# Oda_Lambas_V0_01.net
KiCad netlist of a schematic drawn in EAGLE
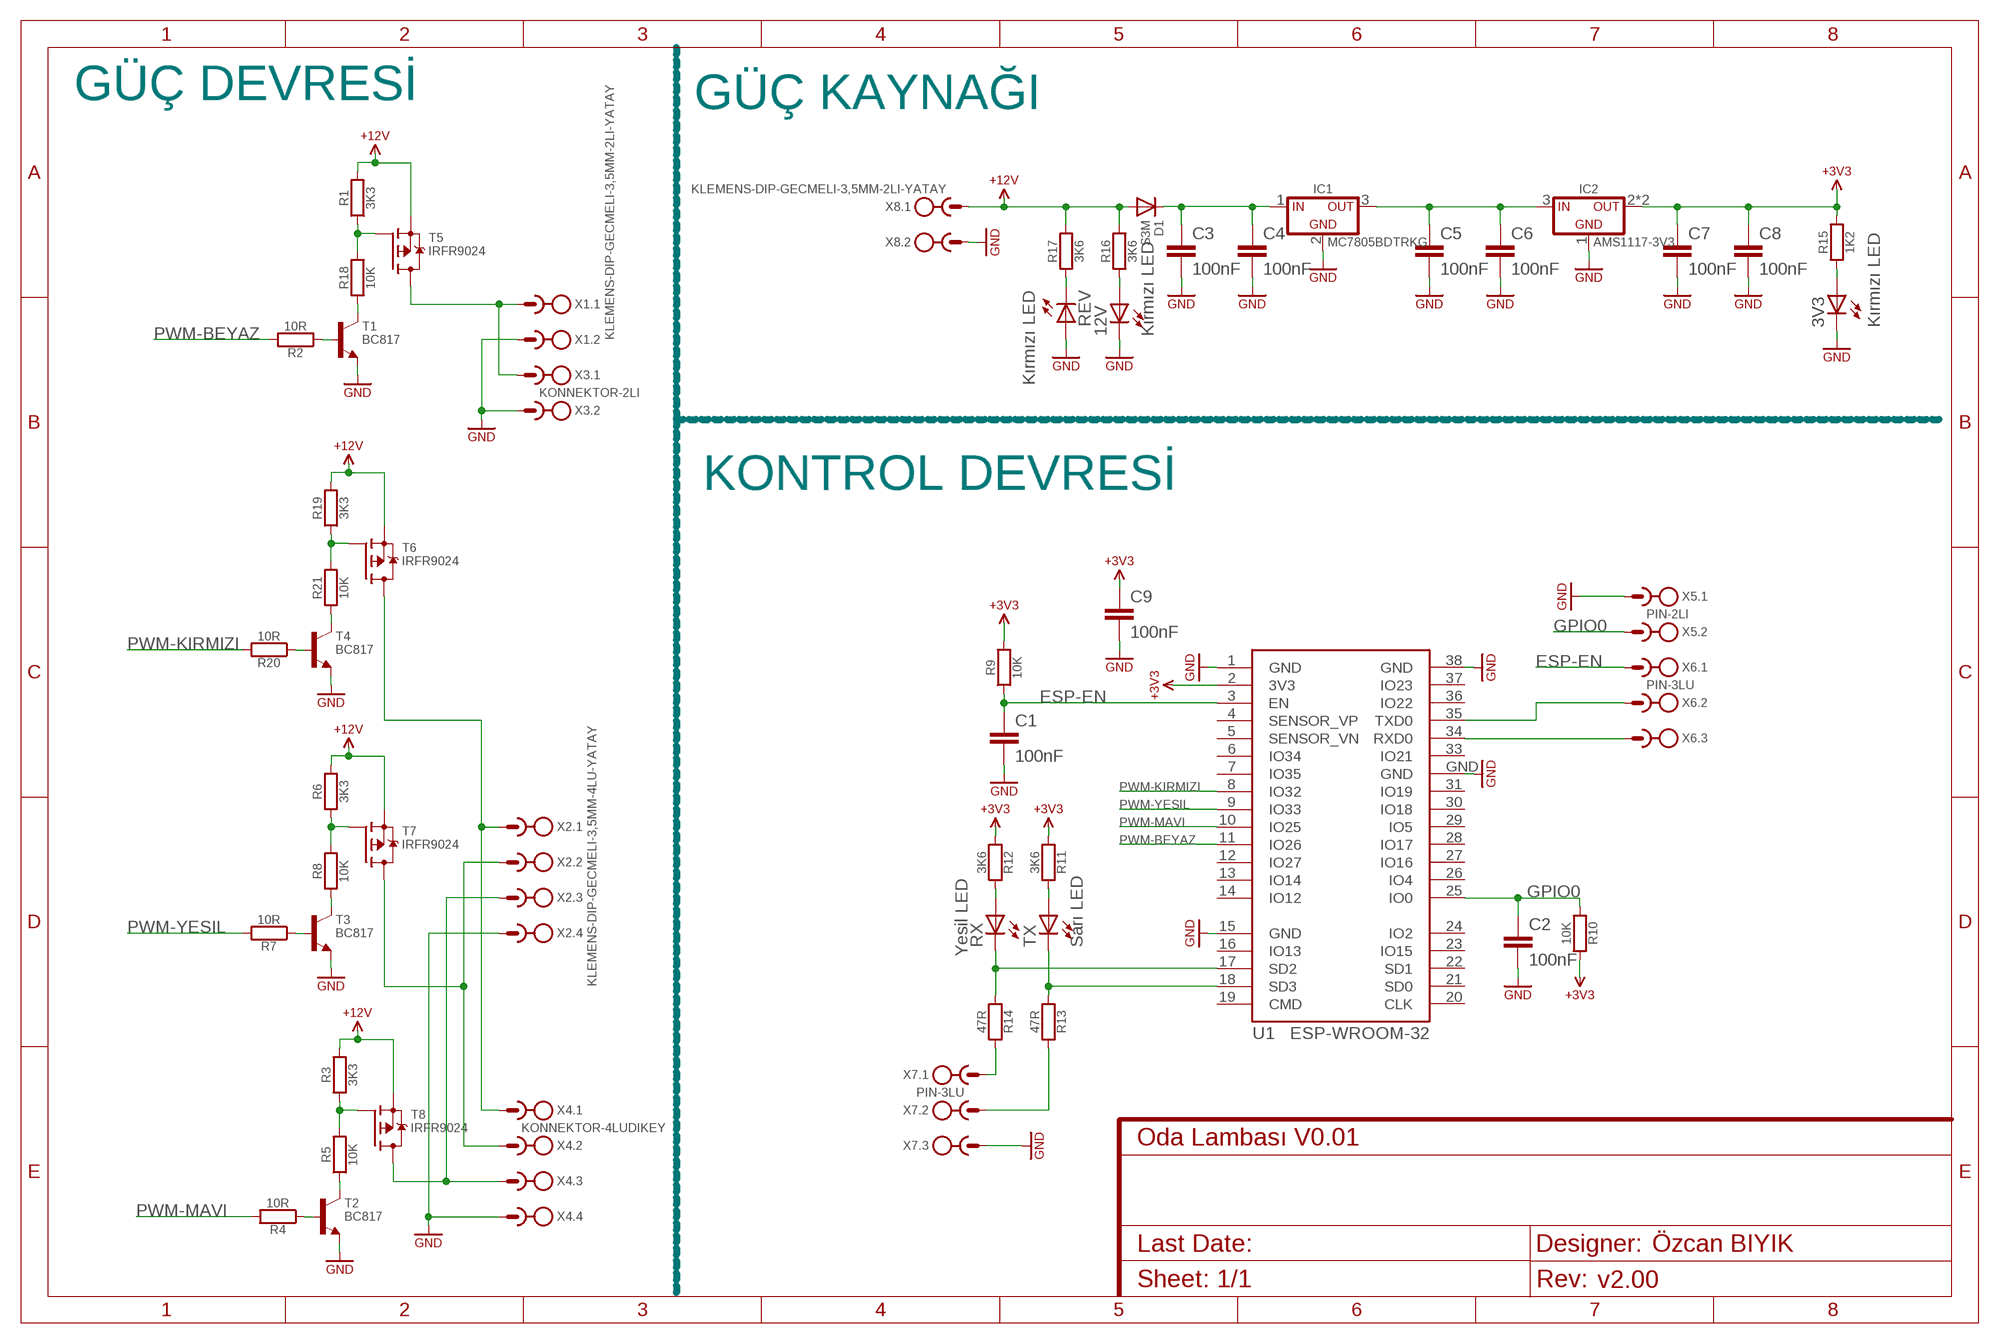
[diagram p0: schematic, sheet 1]

(export (version "E")
  (design (tool "Eeschema 10.0.6"))
  (components
    (comp (ref "3V3")
      (value "Kırmızı LED")
      (footprint "eagle-import:0805")
      (libsource (lib "eagle-import") (part "LED"))
    )
    (comp (ref "12V")
      (value "Kırmızı LED")
      (footprint "eagle-import:0805")
      (libsource (lib "eagle-import") (part "LED"))
    )
    (comp (ref "C1")
      (value "100nF")
      (footprint "eagle-import:C1206")
      (libsource (lib "eagle-import") (part "CAP1206"))
    )
    (comp (ref "C2")
      (value "100nF")
      (footprint "eagle-import:C1206")
      (libsource (lib "eagle-import") (part "CAP1206"))
    )
    (comp (ref "C3")
      (value "100nF")
      (footprint "eagle-import:C1206")
      (libsource (lib "eagle-import") (part "CAP1206"))
    )
    (comp (ref "C4")
      (value "100nF")
      (footprint "eagle-import:C1206")
      (libsource (lib "eagle-import") (part "CAP1206"))
    )
    (comp (ref "C5")
      (value "100nF")
      (footprint "eagle-import:C1206")
      (libsource (lib "eagle-import") (part "CAP1206"))
    )
    (comp (ref "C6")
      (value "100nF")
      (footprint "eagle-import:C1206")
      (libsource (lib "eagle-import") (part "CAP1206"))
    )
    (comp (ref "C7")
      (value "100nF")
      (footprint "eagle-import:C1206")
      (libsource (lib "eagle-import") (part "CAP1206"))
    )
    (comp (ref "C8")
      (value "100nF")
      (footprint "eagle-import:C1206")
      (libsource (lib "eagle-import") (part "CAP1206"))
    )
    (comp (ref "C9")
      (value "100nF")
      (footprint "eagle-import:C1206")
      (libsource (lib "eagle-import") (part "CAP1206"))
    )
    (comp (ref "D1")
      (value "S3M")
      (footprint "eagle-import:SMC")
      (libsource (lib "eagle-import") (part "S3M"))
    )
    (comp (ref "IC1")
      (value "MC7805BDTRKG")
      (footprint "eagle-import:DPAK")
      (libsource (lib "eagle-import") (part "MC7805BDTRKG"))
    )
    (comp (ref "IC2")
      (value "AMS1117-3V3")
      (footprint "eagle-import:SOT223")
      (libsource (lib "eagle-import") (part "FAN1117A"))
    )
    (comp (ref "R1")
      (value "3K3")
      (footprint "eagle-import:R1206")
      (libsource (lib "eagle-import") (part "RES1206"))
    )
    (comp (ref "R2")
      (value "10R")
      (footprint "eagle-import:R1206")
      (libsource (lib "eagle-import") (part "RES1206"))
    )
    (comp (ref "R3")
      (value "3K3")
      (footprint "eagle-import:R1206")
      (libsource (lib "eagle-import") (part "RES1206"))
    )
    (comp (ref "R4")
      (value "10R")
      (footprint "eagle-import:R1206")
      (libsource (lib "eagle-import") (part "RES1206"))
    )
    (comp (ref "R5")
      (value "10K")
      (footprint "eagle-import:R1206")
      (libsource (lib "eagle-import") (part "RES1206"))
    )
    (comp (ref "R6")
      (value "3K3")
      (footprint "eagle-import:R1206")
      (libsource (lib "eagle-import") (part "RES1206"))
    )
    (comp (ref "R7")
      (value "10R")
      (footprint "eagle-import:R1206")
      (libsource (lib "eagle-import") (part "RES1206"))
    )
    (comp (ref "R8")
      (value "10K")
      (footprint "eagle-import:R1206")
      (libsource (lib "eagle-import") (part "RES1206"))
    )
    (comp (ref "R9")
      (value "10K")
      (footprint "eagle-import:R1206")
      (libsource (lib "eagle-import") (part "RES1206"))
    )
    (comp (ref "R10")
      (value "10K")
      (footprint "eagle-import:R1206")
      (libsource (lib "eagle-import") (part "RES1206"))
    )
    (comp (ref "R11")
      (value "3K6")
      (footprint "eagle-import:R1206")
      (libsource (lib "eagle-import") (part "RES1206"))
    )
    (comp (ref "R12")
      (value "3K6")
      (footprint "eagle-import:R1206")
      (libsource (lib "eagle-import") (part "RES1206"))
    )
    (comp (ref "R13")
      (value "47R")
      (footprint "eagle-import:R1206")
      (libsource (lib "eagle-import") (part "RES1206"))
    )
    (comp (ref "R14")
      (value "47R")
      (footprint "eagle-import:R1206")
      (libsource (lib "eagle-import") (part "RES1206"))
    )
    (comp (ref "R15")
      (value "1K2")
      (footprint "eagle-import:R1206")
      (libsource (lib "eagle-import") (part "RES1206"))
    )
    (comp (ref "R16")
      (value "3K6")
      (footprint "eagle-import:R1206")
      (libsource (lib "eagle-import") (part "RES1206"))
    )
    (comp (ref "R17")
      (value "3K6")
      (footprint "eagle-import:R1206")
      (libsource (lib "eagle-import") (part "RES1206"))
    )
    (comp (ref "R18")
      (value "10K")
      (footprint "eagle-import:R1206")
      (libsource (lib "eagle-import") (part "RES1206"))
    )
    (comp (ref "R19")
      (value "3K3")
      (footprint "eagle-import:R1206")
      (libsource (lib "eagle-import") (part "RES1206"))
    )
    (comp (ref "R20")
      (value "10R")
      (footprint "eagle-import:R1206")
      (libsource (lib "eagle-import") (part "RES1206"))
    )
    (comp (ref "R21")
      (value "10K")
      (footprint "eagle-import:R1206")
      (libsource (lib "eagle-import") (part "RES1206"))
    )
    (comp (ref "REV")
      (value "Kırmızı LED")
      (footprint "eagle-import:0805")
      (libsource (lib "eagle-import") (part "LED"))
    )
    (comp (ref "RX")
      (value "Yesil LED")
      (footprint "eagle-import:0805")
      (libsource (lib "eagle-import") (part "LED"))
    )
    (comp (ref "T1")
      (value "BC817")
      (footprint "eagle-import:SOT23")
      (libsource (lib "eagle-import") (part "BC817"))
    )
    (comp (ref "T2")
      (value "BC817")
      (footprint "eagle-import:SOT23")
      (libsource (lib "eagle-import") (part "BC817"))
    )
    (comp (ref "T3")
      (value "BC817")
      (footprint "eagle-import:SOT23")
      (libsource (lib "eagle-import") (part "BC817"))
    )
    (comp (ref "T4")
      (value "BC817")
      (footprint "eagle-import:SOT23")
      (libsource (lib "eagle-import") (part "BC817"))
    )
    (comp (ref "T5")
      (value "IRFR9024")
      (footprint "eagle-import:DPAK")
      (libsource (lib "eagle-import") (part "IRFR9024"))
    )
    (comp (ref "T6")
      (value "IRFR9024")
      (footprint "eagle-import:DPAK")
      (libsource (lib "eagle-import") (part "IRFR9024"))
    )
    (comp (ref "T7")
      (value "IRFR9024")
      (footprint "eagle-import:DPAK")
      (libsource (lib "eagle-import") (part "IRFR9024"))
    )
    (comp (ref "T8")
      (value "IRFR9024")
      (footprint "eagle-import:DPAK")
      (libsource (lib "eagle-import") (part "IRFR9024"))
    )
    (comp (ref "TX")
      (value "Sarı LED")
      (footprint "eagle-import:0805")
      (libsource (lib "eagle-import") (part "LED"))
    )
    (comp (ref "U1")
      (value "ESP-WROOM-32")
      (footprint "eagle-import:ESP-WROOM-32")
      (libsource (lib "eagle-import") (part "ESP-WROOM-32"))
    )
    (comp (ref "X1")
      (value "KLEMENS-DIP-GECMELI-3,5MM-2LI-YATAY")
      (footprint "eagle-import:KLEMENS-DIP-GECMELI-3,5MM-2LI-YATAY")
      (libsource (lib "eagle-import") (part "KLEMENS-DIP-GECMELI-3,5MM-2LI-YATAY"))
    )
    (comp (ref "X2")
      (value "KLEMENS-DIP-GECMELI-3,5MM-4LU-YATAY")
      (footprint "eagle-import:KLEMENS-DIP-GECMELI-3,5MM-4LU-YATAY")
      (libsource (lib "eagle-import") (part "KLEMENS-DIP-GECMELI-3,5MM-4LU-YATAY"))
    )
    (comp (ref "X3")
      (value "KONNEKTOR-2LI")
      (footprint "eagle-import:MOLEX-DIP-2LI-YATAY")
      (libsource (lib "eagle-import") (part "KONNEKTOR-2LI"))
    )
    (comp (ref "X4")
      (value "KONNEKTOR-4LUDIKEY")
      (footprint "eagle-import:MOLEX-DIP-4LU-DIKEY")
      (libsource (lib "eagle-import") (part "KONNEKTOR-4LUDIKEY"))
    )
    (comp (ref "X5")
      (value "PIN-2LI")
      (footprint "eagle-import:PINHEADER-DIP-2-2.54")
      (libsource (lib "eagle-import") (part "PIN-2LI"))
    )
    (comp (ref "X6")
      (value "PIN-3LU")
      (footprint "eagle-import:PINHEADER-DIP-3-2.54")
      (libsource (lib "eagle-import") (part "PIN-3LU"))
    )
    (comp (ref "X7")
      (value "PIN-3LU")
      (footprint "eagle-import:PINHEADER-DIP-3-2.54")
      (libsource (lib "eagle-import") (part "PIN-3LU"))
    )
    (comp (ref "X8")
      (value "KLEMENS-DIP-GECMELI-3,5MM-2LI-YATAY")
      (footprint "eagle-import:KLEMENS-DIP-GECMELI-3,5MM-2LI-YATAY")
      (libsource (lib "eagle-import") (part "KLEMENS-DIP-GECMELI-3,5MM-2LI-YATAY"))
    )
  )
  (nets
    (net (code "1") (name "+3V3") (class "Default")
      (node (ref "C7") (pin "1") (pinfunction "1_1") (pintype "passive"))
      (node (ref "C8") (pin "1") (pinfunction "1_1") (pintype "passive"))
      (node (ref "C9") (pin "1") (pinfunction "1_1") (pintype "passive"))
      (node (ref "IC2") (pin "2") (pinfunction "OUT_2") (pintype "passive"))
      (node (ref "IC2") (pin "4") (pinfunction "OUT_4") (pintype "passive"))
      (node (ref "R10") (pin "2") (pinfunction "2_2") (pintype "passive"))
      (node (ref "R11") (pin "2") (pinfunction "2_2") (pintype "passive"))
      (node (ref "R12") (pin "2") (pinfunction "2_2") (pintype "passive"))
      (node (ref "R15") (pin "2") (pinfunction "2_2") (pintype "passive"))
      (node (ref "R9") (pin "2") (pinfunction "2_2") (pintype "passive"))
      (node (ref "U1") (pin "2") (pinfunction "3V3_2") (pintype "power_in"))
    )
    (net (code "2") (name "+12V") (class "Default")
      (node (ref "D1") (pin "A") (pinfunction "A_A") (pintype "passive"))
      (node (ref "R1") (pin "2") (pinfunction "2_2") (pintype "passive"))
      (node (ref "R16") (pin "2") (pinfunction "2_2") (pintype "passive"))
      (node (ref "R17") (pin "2") (pinfunction "2_2") (pintype "passive"))
      (node (ref "R19") (pin "2") (pinfunction "2_2") (pintype "passive"))
      (node (ref "R3") (pin "2") (pinfunction "2_2") (pintype "passive"))
      (node (ref "R6") (pin "2") (pinfunction "2_2") (pintype "passive"))
      (node (ref "T5") (pin "3") (pinfunction "S_3") (pintype "passive"))
      (node (ref "T6") (pin "3") (pinfunction "S_3") (pintype "passive"))
      (node (ref "T7") (pin "3") (pinfunction "S_3") (pintype "passive"))
      (node (ref "T8") (pin "3") (pinfunction "S_3") (pintype "passive"))
      (node (ref "X8") (pin "1") (pinfunction "1_1") (pintype "passive"))
    )
    (net (code "3") (name "/ESP-EN") (class "Default")
      (node (ref "C1") (pin "1") (pinfunction "1_1") (pintype "passive"))
      (node (ref "R9") (pin "1") (pinfunction "1_1") (pintype "passive"))
      (node (ref "U1") (pin "3") (pinfunction "EN_3") (pintype "input"))
      (node (ref "X6") (pin "1") (pinfunction "1_1") (pintype "passive"))
    )
    (net (code "4") (name "/GPIO0") (class "Default")
      (node (ref "C2") (pin "1") (pinfunction "1_1") (pintype "passive"))
      (node (ref "R10") (pin "1") (pinfunction "1_1") (pintype "passive"))
      (node (ref "U1") (pin "25") (pinfunction "IO0_25") (pintype "bidirectional"))
      (node (ref "X5") (pin "2") (pinfunction "1_2") (pintype "passive"))
    )
    (net (code "5") (name "/PWM-BEYAZ") (class "Default")
      (node (ref "R2") (pin "2") (pinfunction "2_2") (pintype "passive"))
      (node (ref "U1") (pin "11") (pinfunction "IO26_11") (pintype "bidirectional"))
    )
    (net (code "6") (name "/PWM-KIRMIZI") (class "Default")
      (node (ref "R20") (pin "2") (pinfunction "2_2") (pintype "passive"))
      (node (ref "U1") (pin "8") (pinfunction "IO32_8") (pintype "bidirectional"))
    )
    (net (code "7") (name "/PWM-MAVI") (class "Default")
      (node (ref "R4") (pin "2") (pinfunction "2_2") (pintype "passive"))
      (node (ref "U1") (pin "10") (pinfunction "IO25_10") (pintype "bidirectional"))
    )
    (net (code "8") (name "/PWM-YESIL") (class "Default")
      (node (ref "R7") (pin "2") (pinfunction "2_2") (pintype "passive"))
      (node (ref "U1") (pin "9") (pinfunction "IO33_9") (pintype "bidirectional"))
    )
    (net (code "9") (name "GND") (class "Default")
      (node (ref "12V") (pin "C") (pinfunction "C_C") (pintype "passive"))
      (node (ref "3V3") (pin "C") (pinfunction "C_C") (pintype "passive"))
      (node (ref "C1") (pin "2") (pinfunction "2_2") (pintype "passive"))
      (node (ref "C2") (pin "2") (pinfunction "2_2") (pintype "passive"))
      (node (ref "C3") (pin "2") (pinfunction "2_2") (pintype "passive"))
      (node (ref "C4") (pin "2") (pinfunction "2_2") (pintype "passive"))
      (node (ref "C5") (pin "2") (pinfunction "2_2") (pintype "passive"))
      (node (ref "C6") (pin "2") (pinfunction "2_2") (pintype "passive"))
      (node (ref "C7") (pin "2") (pinfunction "2_2") (pintype "passive"))
      (node (ref "C8") (pin "2") (pinfunction "2_2") (pintype "passive"))
      (node (ref "C9") (pin "2") (pinfunction "2_2") (pintype "passive"))
      (node (ref "IC1") (pin "2") (pinfunction "GND_2") (pintype "passive"))
      (node (ref "IC2") (pin "1") (pinfunction "GND_1") (pintype "passive"))
      (node (ref "REV") (pin "A") (pinfunction "A_A") (pintype "passive"))
      (node (ref "T1") (pin "2") (pinfunction "E_2") (pintype "passive"))
      (node (ref "T2") (pin "2") (pinfunction "E_2") (pintype "passive"))
      (node (ref "T3") (pin "2") (pinfunction "E_2") (pintype "passive"))
      (node (ref "T4") (pin "2") (pinfunction "E_2") (pintype "passive"))
      (node (ref "U1") (pin "1") (pinfunction "GND_1") (pintype "power_in"))
      (node (ref "U1") (pin "15") (pinfunction "GND_15") (pintype "power_in"))
      (node (ref "U1") (pin "38") (pinfunction "GND_38") (pintype "power_in"))
      (node (ref "U1") (pin "GND") (pinfunction "GND_GND") (pintype "power_in"))
      (node (ref "X1") (pin "2") (pinfunction "1_2") (pintype "passive"))
      (node (ref "X2") (pin "4") (pinfunction "1_4") (pintype "passive"))
      (node (ref "X3") (pin "2") (pinfunction "1_2") (pintype "passive"))
      (node (ref "X4") (pin "4") (pinfunction "1_4") (pintype "passive"))
      (node (ref "X5") (pin "1") (pinfunction "1_1") (pintype "passive"))
      (node (ref "X7") (pin "3") (pinfunction "1_3") (pintype "passive"))
      (node (ref "X8") (pin "2") (pinfunction "1_2") (pintype "passive"))
    )
    (net (code "10") (name "Net-(3V3-PadA)") (class "Default")
      (node (ref "3V3") (pin "A") (pinfunction "A_A") (pintype "passive"))
      (node (ref "R15") (pin "1") (pinfunction "1_1") (pintype "passive"))
    )
    (net (code "11") (name "Net-(12V-PadA)") (class "Default")
      (node (ref "12V") (pin "A") (pinfunction "A_A") (pintype "passive"))
      (node (ref "R16") (pin "1") (pinfunction "1_1") (pintype "passive"))
    )
    (net (code "12") (name "Net-(IC1-IN)") (class "Default")
      (node (ref "C3") (pin "1") (pinfunction "1_1") (pintype "passive"))
      (node (ref "C4") (pin "1") (pinfunction "1_1") (pintype "passive"))
      (node (ref "D1") (pin "C") (pinfunction "C_C") (pintype "passive"))
      (node (ref "IC1") (pin "1") (pinfunction "IN_1") (pintype "passive"))
    )
    (net (code "13") (name "Net-(IC1-OUT)") (class "Default")
      (node (ref "C5") (pin "1") (pinfunction "1_1") (pintype "passive"))
      (node (ref "C6") (pin "1") (pinfunction "1_1") (pintype "passive"))
      (node (ref "IC1") (pin "3") (pinfunction "OUT_3") (pintype "passive"))
      (node (ref "IC2") (pin "3") (pinfunction "IN_3") (pintype "passive"))
    )
    (net (code "14") (name "Net-(R11-Pad1)") (class "Default")
      (node (ref "R11") (pin "1") (pinfunction "1_1") (pintype "passive"))
      (node (ref "TX") (pin "A") (pinfunction "A_A") (pintype "passive"))
    )
    (net (code "15") (name "Net-(R12-Pad1)") (class "Default")
      (node (ref "R12") (pin "1") (pinfunction "1_1") (pintype "passive"))
      (node (ref "RX") (pin "A") (pinfunction "A_A") (pintype "passive"))
    )
    (net (code "16") (name "Net-(R14-Pad1)") (class "Default")
      (node (ref "R14") (pin "1") (pinfunction "1_1") (pintype "passive"))
      (node (ref "X7") (pin "1") (pinfunction "1_1") (pintype "passive"))
    )
    (net (code "17") (name "Net-(R17-Pad1)") (class "Default")
      (node (ref "R17") (pin "1") (pinfunction "1_1") (pintype "passive"))
      (node (ref "REV") (pin "C") (pinfunction "C_C") (pintype "passive"))
    )
    (net (code "18") (name "Net-(T1-B)") (class "Default")
      (node (ref "R2") (pin "1") (pinfunction "1_1") (pintype "passive"))
      (node (ref "T1") (pin "1") (pinfunction "B_1") (pintype "passive"))
    )
    (net (code "19") (name "Net-(T1-C)") (class "Default")
      (node (ref "R18") (pin "1") (pinfunction "1_1") (pintype "passive"))
      (node (ref "T1") (pin "3") (pinfunction "C_3") (pintype "passive"))
    )
    (net (code "20") (name "Net-(T2-B)") (class "Default")
      (node (ref "R4") (pin "1") (pinfunction "1_1") (pintype "passive"))
      (node (ref "T2") (pin "1") (pinfunction "B_1") (pintype "passive"))
    )
    (net (code "21") (name "Net-(T2-C)") (class "Default")
      (node (ref "R5") (pin "1") (pinfunction "1_1") (pintype "passive"))
      (node (ref "T2") (pin "3") (pinfunction "C_3") (pintype "passive"))
    )
    (net (code "22") (name "Net-(T3-B)") (class "Default")
      (node (ref "R7") (pin "1") (pinfunction "1_1") (pintype "passive"))
      (node (ref "T3") (pin "1") (pinfunction "B_1") (pintype "passive"))
    )
    (net (code "23") (name "Net-(T3-C)") (class "Default")
      (node (ref "R8") (pin "1") (pinfunction "1_1") (pintype "passive"))
      (node (ref "T3") (pin "3") (pinfunction "C_3") (pintype "passive"))
    )
    (net (code "24") (name "Net-(T4-B)") (class "Default")
      (node (ref "R20") (pin "1") (pinfunction "1_1") (pintype "passive"))
      (node (ref "T4") (pin "1") (pinfunction "B_1") (pintype "passive"))
    )
    (net (code "25") (name "Net-(T4-C)") (class "Default")
      (node (ref "R21") (pin "1") (pinfunction "1_1") (pintype "passive"))
      (node (ref "T4") (pin "3") (pinfunction "C_3") (pintype "passive"))
    )
    (net (code "26") (name "Net-(T5-D)") (class "Default")
      (node (ref "T5") (pin "2") (pinfunction "D_2") (pintype "passive"))
      (node (ref "X1") (pin "1") (pinfunction "1_1") (pintype "passive"))
      (node (ref "X3") (pin "1") (pinfunction "1_1") (pintype "passive"))
    )
    (net (code "27") (name "Net-(T5-G)") (class "Default")
      (node (ref "R1") (pin "1") (pinfunction "1_1") (pintype "passive"))
      (node (ref "R18") (pin "2") (pinfunction "2_2") (pintype "passive"))
      (node (ref "T5") (pin "1") (pinfunction "G_1") (pintype "passive"))
    )
    (net (code "28") (name "Net-(T6-D)") (class "Default")
      (node (ref "T6") (pin "2") (pinfunction "D_2") (pintype "passive"))
      (node (ref "X2") (pin "1") (pinfunction "1_1") (pintype "passive"))
      (node (ref "X4") (pin "1") (pinfunction "1_1") (pintype "passive"))
    )
    (net (code "29") (name "Net-(T6-G)") (class "Default")
      (node (ref "R19") (pin "1") (pinfunction "1_1") (pintype "passive"))
      (node (ref "R21") (pin "2") (pinfunction "2_2") (pintype "passive"))
      (node (ref "T6") (pin "1") (pinfunction "G_1") (pintype "passive"))
    )
    (net (code "30") (name "Net-(T7-D)") (class "Default")
      (node (ref "T7") (pin "2") (pinfunction "D_2") (pintype "passive"))
      (node (ref "X2") (pin "2") (pinfunction "1_2") (pintype "passive"))
      (node (ref "X4") (pin "2") (pinfunction "1_2") (pintype "passive"))
    )
    (net (code "31") (name "Net-(T7-G)") (class "Default")
      (node (ref "R6") (pin "1") (pinfunction "1_1") (pintype "passive"))
      (node (ref "R8") (pin "2") (pinfunction "2_2") (pintype "passive"))
      (node (ref "T7") (pin "1") (pinfunction "G_1") (pintype "passive"))
    )
    (net (code "32") (name "Net-(T8-D)") (class "Default")
      (node (ref "T8") (pin "2") (pinfunction "D_2") (pintype "passive"))
      (node (ref "X2") (pin "3") (pinfunction "1_3") (pintype "passive"))
      (node (ref "X4") (pin "3") (pinfunction "1_3") (pintype "passive"))
    )
    (net (code "33") (name "Net-(T8-G)") (class "Default")
      (node (ref "R3") (pin "1") (pinfunction "1_1") (pintype "passive"))
      (node (ref "R5") (pin "2") (pinfunction "2_2") (pintype "passive"))
      (node (ref "T8") (pin "1") (pinfunction "G_1") (pintype "passive"))
    )
    (net (code "34") (name "Net-(U1-RXD0)") (class "Default")
      (node (ref "U1") (pin "34") (pinfunction "RXD0_34") (pintype "bidirectional"))
      (node (ref "X6") (pin "3") (pinfunction "1_3") (pintype "passive"))
    )
    (net (code "35") (name "Net-(U1-SD2)") (class "Default")
      (node (ref "R14") (pin "2") (pinfunction "2_2") (pintype "passive"))
      (node (ref "RX") (pin "C") (pinfunction "C_C") (pintype "passive"))
      (node (ref "U1") (pin "17") (pinfunction "SD2_17") (pintype "bidirectional"))
    )
    (net (code "36") (name "Net-(U1-SD3)") (class "Default")
      (node (ref "R13") (pin "2") (pinfunction "2_2") (pintype "passive"))
      (node (ref "TX") (pin "C") (pinfunction "C_C") (pintype "passive"))
      (node (ref "U1") (pin "18") (pinfunction "SD3_18") (pintype "bidirectional"))
    )
    (net (code "37") (name "Net-(U1-TXD0)") (class "Default")
      (node (ref "U1") (pin "35") (pinfunction "TXD0_35") (pintype "bidirectional"))
      (node (ref "X6") (pin "2") (pinfunction "1_2") (pintype "passive"))
    )
    (net (code "38") (name "Net-(X7B-1)") (class "Default")
      (node (ref "R13") (pin "1") (pinfunction "1_1") (pintype "passive"))
      (node (ref "X7") (pin "2") (pinfunction "1_2") (pintype "passive"))
    )
    (net (code "39") (name "unconnected-(U1-CLK-Pad20)") (class "Default")
      (node (ref "U1") (pin "20") (pinfunction "CLK_20") (pintype "bidirectional"))
    )
    (net (code "40") (name "unconnected-(U1-CMD-Pad19)") (class "Default")
      (node (ref "U1") (pin "19") (pinfunction "CMD_19") (pintype "bidirectional"))
    )
    (net (code "41") (name "unconnected-(U1-IO2-Pad24)") (class "Default")
      (node (ref "U1") (pin "24") (pinfunction "IO2_24") (pintype "bidirectional"))
    )
    (net (code "42") (name "unconnected-(U1-IO4-Pad26)") (class "Default")
      (node (ref "U1") (pin "26") (pinfunction "IO4_26") (pintype "bidirectional"))
    )
    (net (code "43") (name "unconnected-(U1-IO5-Pad29)") (class "Default")
      (node (ref "U1") (pin "29") (pinfunction "IO5_29") (pintype "bidirectional"))
    )
    (net (code "44") (name "unconnected-(U1-IO12-Pad14)") (class "Default")
      (node (ref "U1") (pin "14") (pinfunction "IO12_14") (pintype "bidirectional"))
    )
    (net (code "45") (name "unconnected-(U1-IO13-Pad16)") (class "Default")
      (node (ref "U1") (pin "16") (pinfunction "IO13_16") (pintype "bidirectional"))
    )
    (net (code "46") (name "unconnected-(U1-IO14-Pad13)") (class "Default")
      (node (ref "U1") (pin "13") (pinfunction "IO14_13") (pintype "bidirectional"))
    )
    (net (code "47") (name "unconnected-(U1-IO15-Pad23)") (class "Default")
      (node (ref "U1") (pin "23") (pinfunction "IO15_23") (pintype "bidirectional"))
    )
    (net (code "48") (name "unconnected-(U1-IO16-Pad27)") (class "Default")
      (node (ref "U1") (pin "27") (pinfunction "IO16_27") (pintype "bidirectional"))
    )
    (net (code "49") (name "unconnected-(U1-IO17-Pad28)") (class "Default")
      (node (ref "U1") (pin "28") (pinfunction "IO17_28") (pintype "bidirectional"))
    )
    (net (code "50") (name "unconnected-(U1-IO18-Pad30)") (class "Default")
      (node (ref "U1") (pin "30") (pinfunction "IO18_30") (pintype "bidirectional"))
    )
    (net (code "51") (name "unconnected-(U1-IO19-Pad31)") (class "Default")
      (node (ref "U1") (pin "31") (pinfunction "IO19_31") (pintype "bidirectional"))
    )
    (net (code "52") (name "unconnected-(U1-IO21-Pad33)") (class "Default")
      (node (ref "U1") (pin "33") (pinfunction "IO21_33") (pintype "bidirectional"))
    )
    (net (code "53") (name "unconnected-(U1-IO22-Pad36)") (class "Default")
      (node (ref "U1") (pin "36") (pinfunction "IO22_36") (pintype "bidirectional"))
    )
    (net (code "54") (name "unconnected-(U1-IO23-Pad37)") (class "Default")
      (node (ref "U1") (pin "37") (pinfunction "IO23_37") (pintype "bidirectional"))
    )
    (net (code "55") (name "unconnected-(U1-IO27-Pad12)") (class "Default")
      (node (ref "U1") (pin "12") (pinfunction "IO27_12") (pintype "bidirectional"))
    )
    (net (code "56") (name "unconnected-(U1-IO34-Pad6)") (class "Default")
      (node (ref "U1") (pin "6") (pinfunction "IO34_6") (pintype "bidirectional"))
    )
    (net (code "57") (name "unconnected-(U1-IO35-Pad7)") (class "Default")
      (node (ref "U1") (pin "7") (pinfunction "IO35_7") (pintype "bidirectional"))
    )
    (net (code "58") (name "unconnected-(U1-SD0-Pad21)") (class "Default")
      (node (ref "U1") (pin "21") (pinfunction "SD0_21") (pintype "bidirectional"))
    )
    (net (code "59") (name "unconnected-(U1-SD1-Pad22)") (class "Default")
      (node (ref "U1") (pin "22") (pinfunction "SD1_22") (pintype "bidirectional"))
    )
    (net (code "60") (name "unconnected-(U1-SENSOR_VN-Pad5)") (class "Default")
      (node (ref "U1") (pin "5") (pinfunction "SENSOR_VN_5") (pintype "bidirectional"))
    )
    (net (code "61") (name "unconnected-(U1-SENSOR_VP-Pad4)") (class "Default")
      (node (ref "U1") (pin "4") (pinfunction "SENSOR_VP_4") (pintype "bidirectional"))
    )
  )
)
